# MPU6050_technical_schematic.net
KiCad netlist of a schematic drawn in EasyEDA
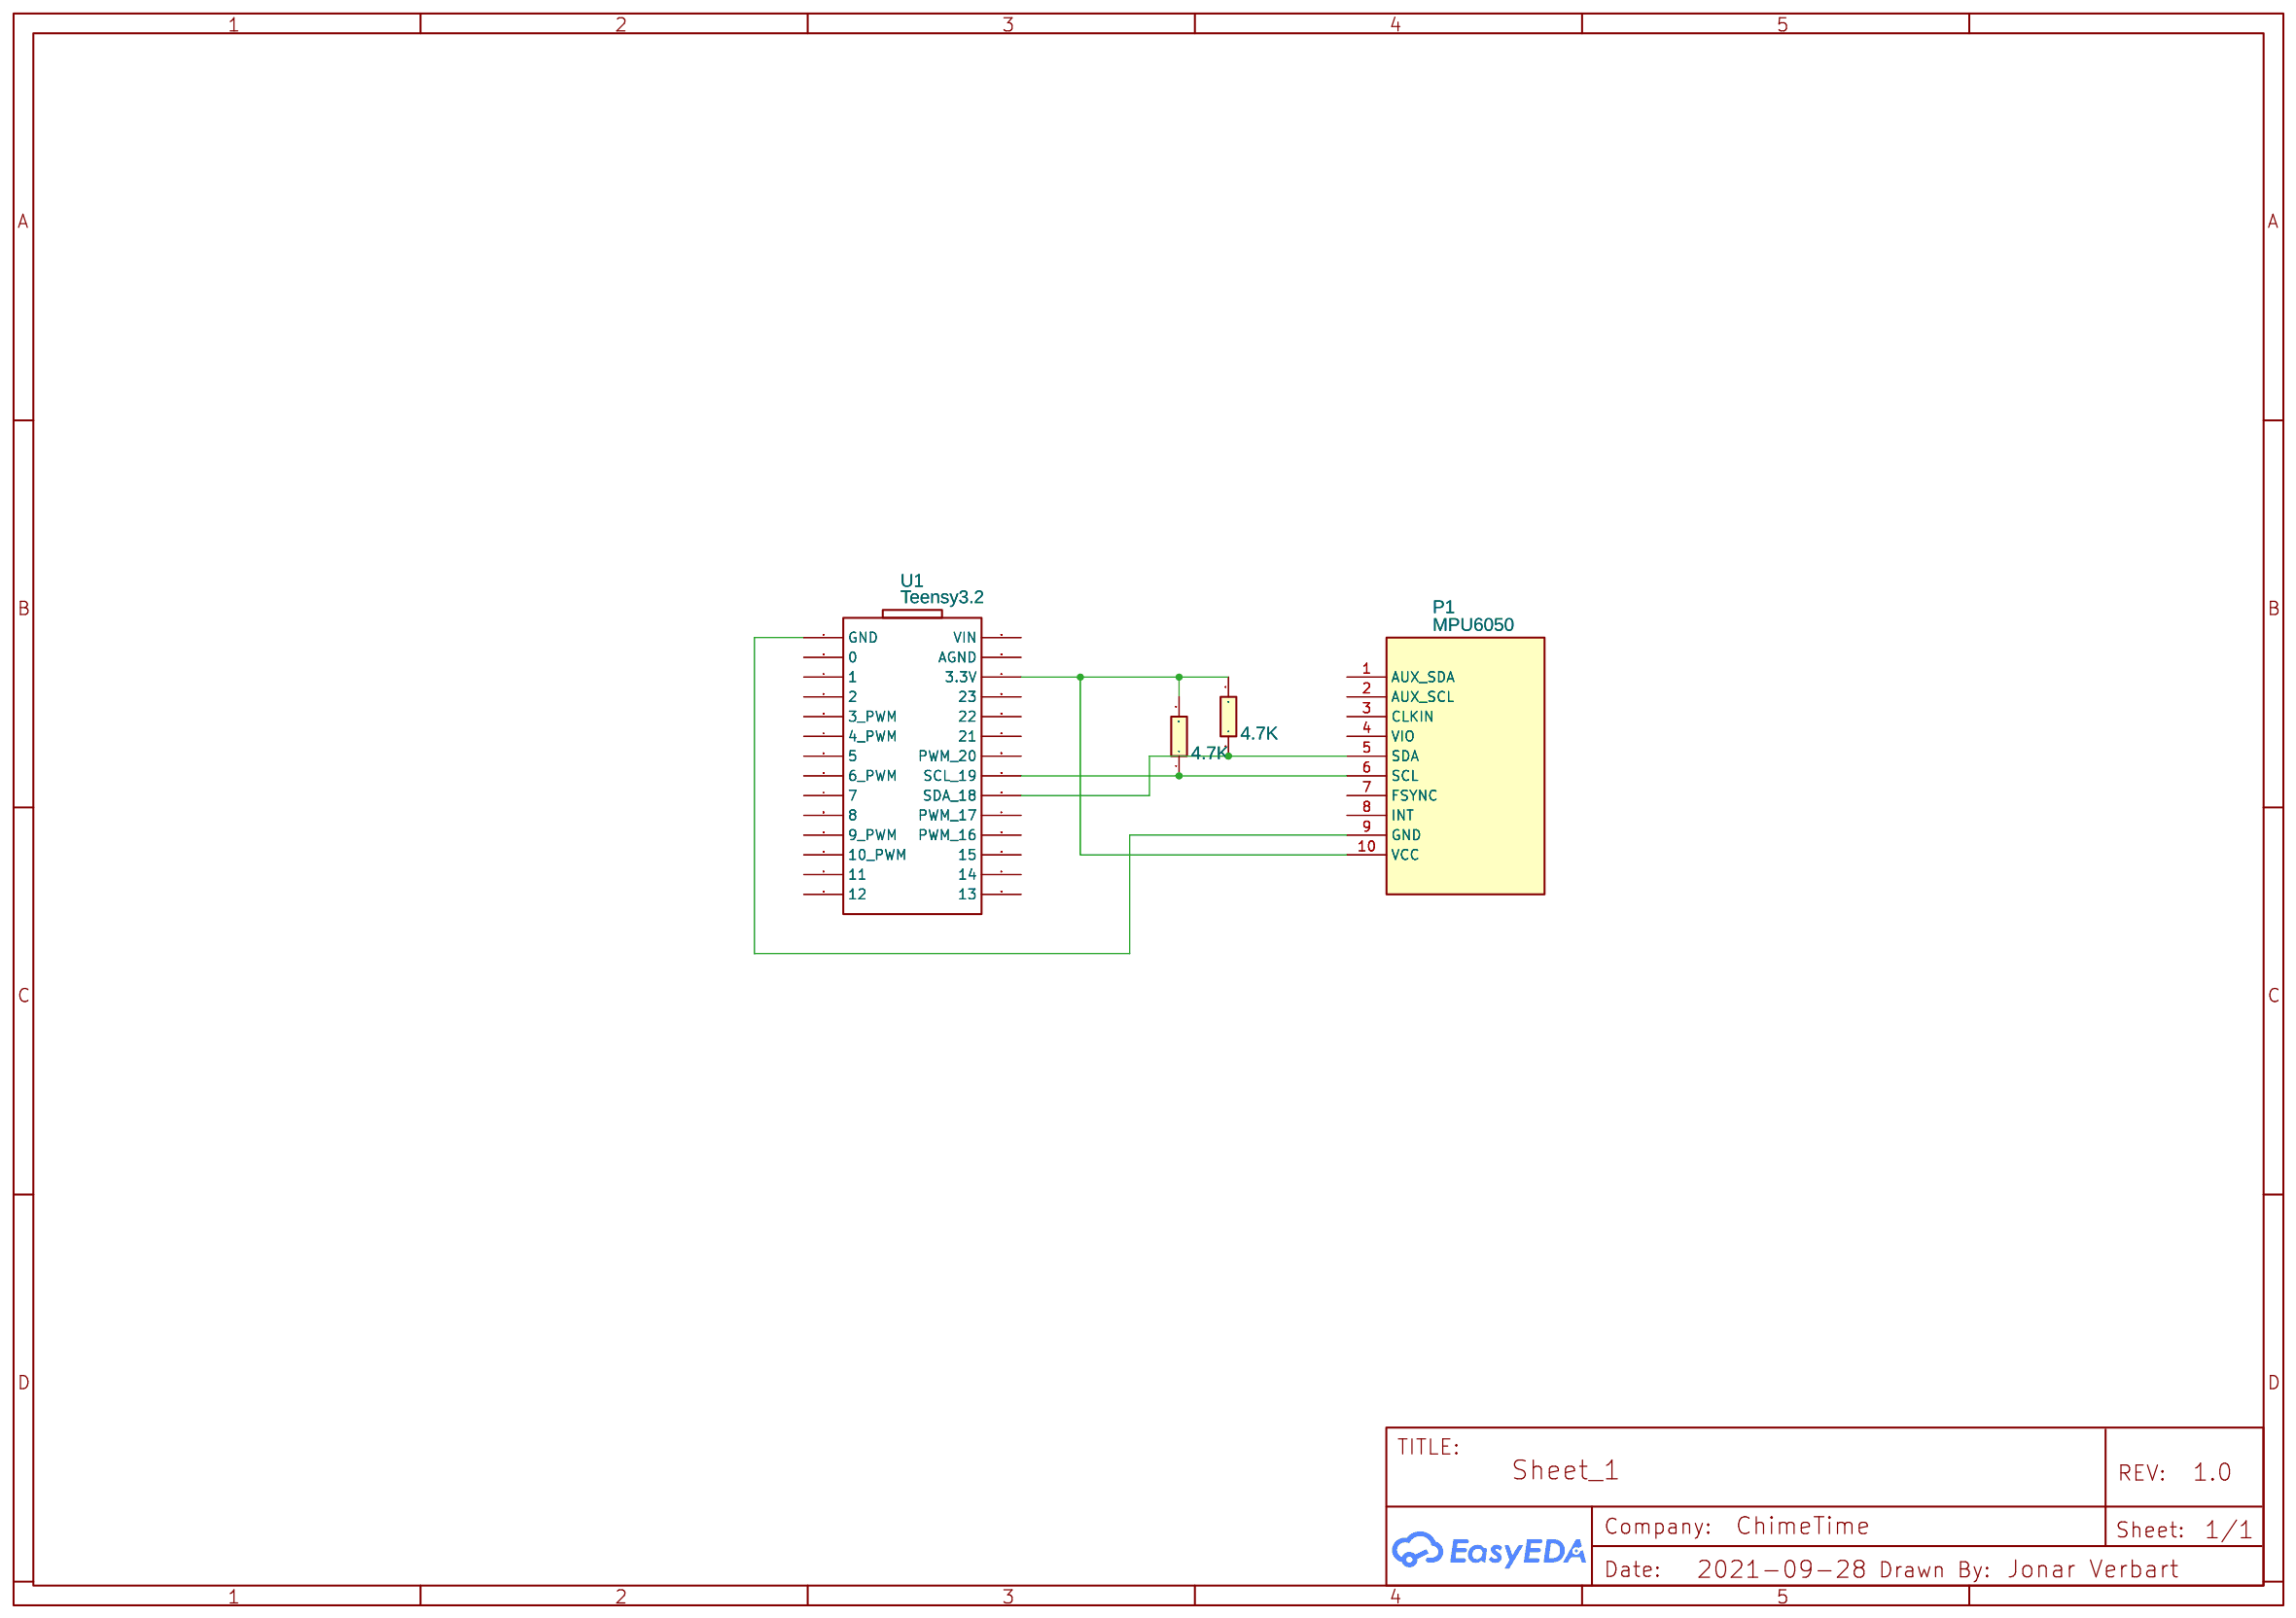
[diagram p0: schematic sheet]

(export (version "E")
  (design (tool "Eeschema 10.0.6"))
  (components
    (comp (ref "4.7K") (value "4.7K") (libsource (lib "") (part "L0603_EU_1")))
    (comp (ref "L2") (value "4.7K") (libsource (lib "") (part "L0603_EU")))
    (comp (ref "P1") (value "MPU6050") (libsource (lib "") (part "MPU6050")))
    (comp (ref "U1")
      (value "Teensy3.2")
      (fields (field (name "BOM_Manufacturer Part") "Teensy 3.2"))
      (libsource (lib "") (part "Teensy3.2"))
    )
  )
  (nets
    (net (code "1") (name "Net-(P1-GND)") (class "Default")
      (node (ref "P1") (pin "9") (pinfunction "GND_9") (pintype "unspecified"))
      (node (ref "U1") (pin "27") (pinfunction "GND_27") (pintype "unspecified"))
    )
    (net (code "2") (name "Net-(P1-SCL)") (class "Default")
      (node (ref "L2") (pin "1") (pinfunction "1_1") (pintype "unspecified"))
      (node (ref "P1") (pin "6") (pinfunction "SCL_6") (pintype "unspecified"))
      (node (ref "U1") (pin "19") (pinfunction "SCL_19_19") (pintype "unspecified"))
    )
    (net (code "3") (name "Net-(P1-SDA)") (class "Default")
      (node (ref "4.7K") (pin "1") (pinfunction "1_1") (pintype "unspecified"))
      (node (ref "P1") (pin "5") (pinfunction "SDA_5") (pintype "unspecified"))
      (node (ref "U1") (pin "18") (pinfunction "SDA_18_18") (pintype "unspecified"))
    )
    (net (code "4") (name "Net-(P1-VCC)") (class "Default")
      (node (ref "4.7K") (pin "2") (pinfunction "2_2") (pintype "unspecified"))
      (node (ref "L2") (pin "2") (pinfunction "2_2") (pintype "unspecified"))
      (node (ref "P1") (pin "10") (pinfunction "VCC_10") (pintype "unspecified"))
      (node (ref "U1") (pin "24") (pinfunction "3.3V_24") (pintype "unspecified"))
    )
    (net (code "5") (name "unconnected-(P1-AUX_SCL-Pad2)") (class "Default")
      (node (ref "P1") (pin "2") (pinfunction "AUX_SCL_2") (pintype "unspecified"))
    )
    (net (code "6") (name "unconnected-(P1-AUX_SDA-Pad1)") (class "Default")
      (node (ref "P1") (pin "1") (pinfunction "AUX_SDA_1") (pintype "unspecified"))
    )
    (net (code "7") (name "unconnected-(P1-CLKIN-Pad3)") (class "Default")
      (node (ref "P1") (pin "3") (pinfunction "CLKIN_3") (pintype "unspecified"))
    )
    (net (code "8") (name "unconnected-(P1-FSYNC-Pad7)") (class "Default")
      (node (ref "P1") (pin "7") (pinfunction "FSYNC_7") (pintype "unspecified"))
    )
    (net (code "9") (name "unconnected-(P1-INT-Pad8)") (class "Default")
      (node (ref "P1") (pin "8") (pinfunction "INT_8") (pintype "unspecified"))
    )
    (net (code "10") (name "unconnected-(P1-VIO-Pad4)") (class "Default")
      (node (ref "P1") (pin "4") (pinfunction "VIO_4") (pintype "unspecified"))
    )
    (net (code "11") (name "unconnected-(U1-3_PWM-Pad3)") (class "Default")
      (node (ref "U1") (pin "3") (pinfunction "3_PWM_3") (pintype "unspecified"))
    )
    (net (code "12") (name "unconnected-(U1-4_PWM-Pad4)") (class "Default")
      (node (ref "U1") (pin "4") (pinfunction "4_PWM_4") (pintype "unspecified"))
    )
    (net (code "13") (name "unconnected-(U1-6_PWM-Pad6)") (class "Default")
      (node (ref "U1") (pin "6") (pinfunction "6_PWM_6") (pintype "unspecified"))
    )
    (net (code "14") (name "unconnected-(U1-9_PWM-Pad9)") (class "Default")
      (node (ref "U1") (pin "9") (pinfunction "9_PWM_9") (pintype "unspecified"))
    )
    (net (code "15") (name "unconnected-(U1-10_PWM-Pad10)") (class "Default")
      (node (ref "U1") (pin "10") (pinfunction "10_PWM_10") (pintype "unspecified"))
    )
    (net (code "16") (name "unconnected-(U1-AGND-Pad25)") (class "Default")
      (node (ref "U1") (pin "25") (pinfunction "AGND_25") (pintype "unspecified"))
    )
    (net (code "17") (name "unconnected-(U1-PWM_16-Pad16)") (class "Default")
      (node (ref "U1") (pin "16") (pinfunction "PWM_16_16") (pintype "unspecified"))
    )
    (net (code "18") (name "unconnected-(U1-PWM_17-Pad17)") (class "Default")
      (node (ref "U1") (pin "17") (pinfunction "PWM_17_17") (pintype "unspecified"))
    )
    (net (code "19") (name "unconnected-(U1-PWM_20-Pad20)") (class "Default")
      (node (ref "U1") (pin "20") (pinfunction "PWM_20_20") (pintype "unspecified"))
    )
    (net (code "20") (name "unconnected-(U1-Pad0)") (class "Default")
      (node (ref "U1") (pin "0") (pinfunction "0_0") (pintype "unspecified"))
    )
    (net (code "21") (name "unconnected-(U1-Pad1)") (class "Default")
      (node (ref "U1") (pin "1") (pinfunction "1_1") (pintype "unspecified"))
    )
    (net (code "22") (name "unconnected-(U1-Pad2)") (class "Default")
      (node (ref "U1") (pin "2") (pinfunction "2_2") (pintype "unspecified"))
    )
    (net (code "23") (name "unconnected-(U1-Pad5)") (class "Default")
      (node (ref "U1") (pin "5") (pinfunction "5_5") (pintype "unspecified"))
    )
    (net (code "24") (name "unconnected-(U1-Pad7)") (class "Default")
      (node (ref "U1") (pin "7") (pinfunction "7_7") (pintype "unspecified"))
    )
    (net (code "25") (name "unconnected-(U1-Pad8)") (class "Default")
      (node (ref "U1") (pin "8") (pinfunction "8_8") (pintype "unspecified"))
    )
    (net (code "26") (name "unconnected-(U1-Pad11)") (class "Default")
      (node (ref "U1") (pin "11") (pinfunction "11_11") (pintype "unspecified"))
    )
    (net (code "27") (name "unconnected-(U1-Pad12)") (class "Default")
      (node (ref "U1") (pin "12") (pinfunction "12_12") (pintype "unspecified"))
    )
    (net (code "28") (name "unconnected-(U1-Pad13)") (class "Default")
      (node (ref "U1") (pin "13") (pinfunction "13_13") (pintype "unspecified"))
    )
    (net (code "29") (name "unconnected-(U1-Pad14)") (class "Default")
      (node (ref "U1") (pin "14") (pinfunction "14_14") (pintype "unspecified"))
    )
    (net (code "30") (name "unconnected-(U1-Pad15)") (class "Default")
      (node (ref "U1") (pin "15") (pinfunction "15_15") (pintype "unspecified"))
    )
    (net (code "31") (name "unconnected-(U1-Pad21)") (class "Default")
      (node (ref "U1") (pin "21") (pinfunction "21_21") (pintype "unspecified"))
    )
    (net (code "32") (name "unconnected-(U1-Pad22)") (class "Default")
      (node (ref "U1") (pin "22") (pinfunction "22_22") (pintype "unspecified"))
    )
    (net (code "33") (name "unconnected-(U1-Pad23)") (class "Default")
      (node (ref "U1") (pin "23") (pinfunction "23_23") (pintype "unspecified"))
    )
    (net (code "34") (name "unconnected-(U1-VIN-Pad26)") (class "Default")
      (node (ref "U1") (pin "26") (pinfunction "VIN_26") (pintype "unspecified"))
    )
  )
)
